# TermWylPomp1_ds18.net
KiCad netlist of a schematic drawn in Altium Designer
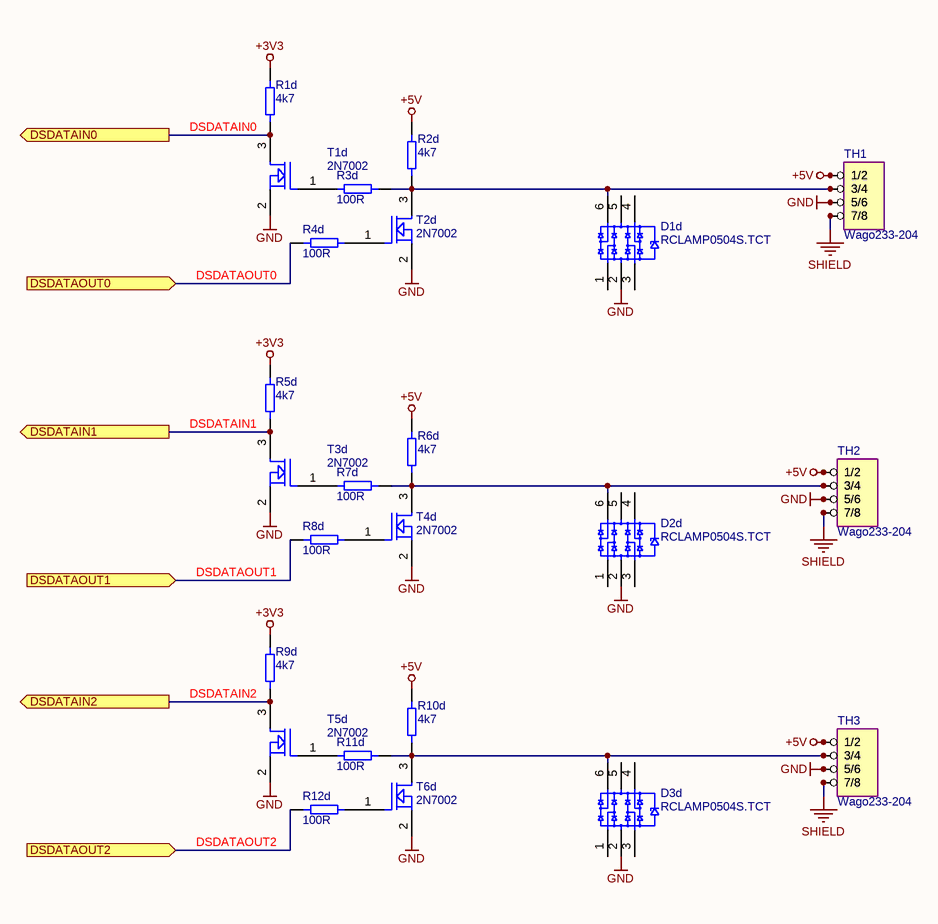
[diagram p0: TermWylPomp1_ds18.SchDoc]

(export (version "E")
  (design (tool "Eeschema 10.0.6"))
  (components
    (comp (ref "D1d")
      (value "RCLAMP0504S.TCT")
      (footprint "SOT23-6")
      (libsource (lib "PartsMySQL") (part "RCLAMP0504"))
    )
    (comp (ref "D2d")
      (value "RCLAMP0504S.TCT")
      (footprint "SOT23-6")
      (libsource (lib "PartsMySQL") (part "RCLAMP0504"))
    )
    (comp (ref "D3d")
      (value "RCLAMP0504S.TCT")
      (footprint "SOT23-6")
      (libsource (lib "PartsMySQL") (part "RCLAMP0504"))
    )
    (comp (ref "R1d") (value "4k7") (footprint "0805R") (libsource (lib "PartsMySQL") (part "R")))
    (comp (ref "R2d") (value "4k7") (footprint "0805R") (libsource (lib "PartsMySQL") (part "R")))
    (comp (ref "R3d") (value "100R") (footprint "0805R") (libsource (lib "PartsMySQL") (part "R")))
    (comp (ref "R4d") (value "100R") (footprint "0805R") (libsource (lib "PartsMySQL") (part "R")))
    (comp (ref "R5d") (value "4k7") (footprint "0805R") (libsource (lib "PartsMySQL") (part "R")))
    (comp (ref "R6d") (value "4k7") (footprint "0805R") (libsource (lib "PartsMySQL") (part "R")))
    (comp (ref "R7d") (value "100R") (footprint "0805R") (libsource (lib "PartsMySQL") (part "R")))
    (comp (ref "R8d") (value "100R") (footprint "0805R") (libsource (lib "PartsMySQL") (part "R")))
    (comp (ref "R9d") (value "4k7") (footprint "0805R") (libsource (lib "PartsMySQL") (part "R")))
    (comp (ref "R10d") (value "4k7") (footprint "0805R") (libsource (lib "PartsMySQL") (part "R")))
    (comp (ref "R11d") (value "100R") (footprint "0805R") (libsource (lib "PartsMySQL") (part "R")))
    (comp (ref "R12d") (value "100R") (footprint "0805R") (libsource (lib "PartsMySQL") (part "R")))
    (comp (ref "T1d")
      (value "2N7002")
      (footprint "SOT23-3")
      (libsource (lib "PartsMySQL") (part "MOSFET_N_SOT23-3"))
    )
    (comp (ref "T2d")
      (value "2N7002")
      (footprint "SOT23-3")
      (libsource (lib "PartsMySQL") (part "MOSFET_N_SOT23-3"))
    )
    (comp (ref "T3d")
      (value "2N7002")
      (footprint "SOT23-3")
      (libsource (lib "PartsMySQL") (part "MOSFET_N_SOT23-3"))
    )
    (comp (ref "T4d")
      (value "2N7002")
      (footprint "SOT23-3")
      (libsource (lib "PartsMySQL") (part "MOSFET_N_SOT23-3"))
    )
    (comp (ref "T5d")
      (value "2N7002")
      (footprint "SOT23-3")
      (libsource (lib "PartsMySQL") (part "MOSFET_N_SOT23-3"))
    )
    (comp (ref "T6d")
      (value "2N7002")
      (footprint "SOT23-3")
      (libsource (lib "PartsMySQL") (part "MOSFET_N_SOT23-3"))
    )
    (comp (ref "TH1")
      (value "Wago233-204")
      (footprint "Wago233-204")
      (libsource (lib "PartsMySQL") (part "Wago233-204"))
    )
    (comp (ref "TH2")
      (value "Wago233-204")
      (footprint "Wago233-204")
      (libsource (lib "PartsMySQL") (part "Wago233-204"))
    )
    (comp (ref "TH3")
      (value "Wago233-204")
      (footprint "Wago233-204")
      (libsource (lib "PartsMySQL") (part "Wago233-204"))
    )
  )
  (nets
    (net (code "1") (name "+3V3") (class "Default")
      (node (ref "R1d") (pin "1") (pinfunction "1_1") (pintype "passive"))
      (node (ref "R5d") (pin "1") (pinfunction "1_1") (pintype "passive"))
      (node (ref "R9d") (pin "1") (pinfunction "1_1") (pintype "passive"))
    )
    (net (code "2") (name "+5V") (class "Default")
      (node (ref "R10d") (pin "1") (pinfunction "1_1") (pintype "passive"))
      (node (ref "R2d") (pin "1") (pinfunction "1_1") (pintype "passive"))
      (node (ref "R6d") (pin "1") (pinfunction "1_1") (pintype "passive"))
      (node (ref "TH1") (pin "1") (pinfunction "1/2_1") (pintype "passive"))
      (node (ref "TH1") (pin "2") (pinfunction "1/2_2") (pintype "passive"))
      (node (ref "TH2") (pin "1") (pinfunction "1/2_1") (pintype "passive"))
      (node (ref "TH2") (pin "2") (pinfunction "1/2_2") (pintype "passive"))
      (node (ref "TH3") (pin "1") (pinfunction "1/2_1") (pintype "passive"))
      (node (ref "TH3") (pin "2") (pinfunction "1/2_2") (pintype "passive"))
    )
    (net (code "3") (name "/DSDATAIN0") (class "Default")
      (node (ref "R1d") (pin "2") (pinfunction "2_2") (pintype "passive"))
      (node (ref "T1d") (pin "3") (pinfunction "DRAIN_3") (pintype "passive"))
    )
    (net (code "4") (name "/DSDATAIN1") (class "Default")
      (node (ref "R5d") (pin "2") (pinfunction "2_2") (pintype "passive"))
      (node (ref "T3d") (pin "3") (pinfunction "DRAIN_3") (pintype "passive"))
    )
    (net (code "5") (name "/DSDATAIN2") (class "Default")
      (node (ref "R9d") (pin "2") (pinfunction "2_2") (pintype "passive"))
      (node (ref "T5d") (pin "3") (pinfunction "DRAIN_3") (pintype "passive"))
    )
    (net (code "6") (name "/DSDATAOUT0") (class "Default")
      (node (ref "R4d") (pin "1") (pinfunction "1_1") (pintype "passive"))
    )
    (net (code "7") (name "/DSDATAOUT1") (class "Default")
      (node (ref "R8d") (pin "1") (pinfunction "1_1") (pintype "passive"))
    )
    (net (code "8") (name "/DSDATAOUT2") (class "Default")
      (node (ref "R12d") (pin "1") (pinfunction "1_1") (pintype "passive"))
    )
    (net (code "9") (name "GND") (class "Default")
      (node (ref "D1d") (pin "2") (pinfunction "2_2") (pintype "passive"))
      (node (ref "D2d") (pin "2") (pinfunction "2_2") (pintype "passive"))
      (node (ref "D3d") (pin "2") (pinfunction "2_2") (pintype "passive"))
      (node (ref "T1d") (pin "2") (pinfunction "SOURCE_2") (pintype "passive"))
      (node (ref "T2d") (pin "2") (pinfunction "SOURCE_2") (pintype "passive"))
      (node (ref "T3d") (pin "2") (pinfunction "SOURCE_2") (pintype "passive"))
      (node (ref "T4d") (pin "2") (pinfunction "SOURCE_2") (pintype "passive"))
      (node (ref "T5d") (pin "2") (pinfunction "SOURCE_2") (pintype "passive"))
      (node (ref "T6d") (pin "2") (pinfunction "SOURCE_2") (pintype "passive"))
      (node (ref "TH1") (pin "5") (pinfunction "5/6_5") (pintype "passive"))
      (node (ref "TH1") (pin "6") (pinfunction "5/6_6") (pintype "passive"))
      (node (ref "TH2") (pin "5") (pinfunction "5/6_5") (pintype "passive"))
      (node (ref "TH2") (pin "6") (pinfunction "5/6_6") (pintype "passive"))
      (node (ref "TH3") (pin "5") (pinfunction "5/6_5") (pintype "passive"))
      (node (ref "TH3") (pin "6") (pinfunction "5/6_6") (pintype "passive"))
    )
    (net (code "10") (name "Net-(T1d-GATE)") (class "Default")
      (node (ref "R3d") (pin "1") (pinfunction "1_1") (pintype "passive"))
      (node (ref "T1d") (pin "1") (pinfunction "GATE_1") (pintype "passive"))
    )
    (net (code "11") (name "Net-(T2d-DRAIN)") (class "Default")
      (node (ref "D1d") (pin "6") (pinfunction "6_6") (pintype "passive"))
      (node (ref "R2d") (pin "2") (pinfunction "2_2") (pintype "passive"))
      (node (ref "R3d") (pin "2") (pinfunction "2_2") (pintype "passive"))
      (node (ref "T2d") (pin "3") (pinfunction "DRAIN_3") (pintype "passive"))
      (node (ref "TH1") (pin "3") (pinfunction "3/4_3") (pintype "passive"))
      (node (ref "TH1") (pin "4") (pinfunction "3/4_4") (pintype "passive"))
    )
    (net (code "12") (name "Net-(T2d-GATE)") (class "Default")
      (node (ref "R4d") (pin "2") (pinfunction "2_2") (pintype "passive"))
      (node (ref "T2d") (pin "1") (pinfunction "GATE_1") (pintype "passive"))
    )
    (net (code "13") (name "Net-(T3d-GATE)") (class "Default")
      (node (ref "R7d") (pin "1") (pinfunction "1_1") (pintype "passive"))
      (node (ref "T3d") (pin "1") (pinfunction "GATE_1") (pintype "passive"))
    )
    (net (code "14") (name "Net-(T4d-DRAIN)") (class "Default")
      (node (ref "D2d") (pin "6") (pinfunction "6_6") (pintype "passive"))
      (node (ref "R6d") (pin "2") (pinfunction "2_2") (pintype "passive"))
      (node (ref "R7d") (pin "2") (pinfunction "2_2") (pintype "passive"))
      (node (ref "T4d") (pin "3") (pinfunction "DRAIN_3") (pintype "passive"))
      (node (ref "TH2") (pin "3") (pinfunction "3/4_3") (pintype "passive"))
      (node (ref "TH2") (pin "4") (pinfunction "3/4_4") (pintype "passive"))
    )
    (net (code "15") (name "Net-(T4d-GATE)") (class "Default")
      (node (ref "R8d") (pin "2") (pinfunction "2_2") (pintype "passive"))
      (node (ref "T4d") (pin "1") (pinfunction "GATE_1") (pintype "passive"))
    )
    (net (code "16") (name "Net-(T5d-GATE)") (class "Default")
      (node (ref "R11d") (pin "1") (pinfunction "1_1") (pintype "passive"))
      (node (ref "T5d") (pin "1") (pinfunction "GATE_1") (pintype "passive"))
    )
    (net (code "17") (name "Net-(T6d-DRAIN)") (class "Default")
      (node (ref "D3d") (pin "6") (pinfunction "6_6") (pintype "passive"))
      (node (ref "R10d") (pin "2") (pinfunction "2_2") (pintype "passive"))
      (node (ref "R11d") (pin "2") (pinfunction "2_2") (pintype "passive"))
      (node (ref "T6d") (pin "3") (pinfunction "DRAIN_3") (pintype "passive"))
      (node (ref "TH3") (pin "3") (pinfunction "3/4_3") (pintype "passive"))
      (node (ref "TH3") (pin "4") (pinfunction "3/4_4") (pintype "passive"))
    )
    (net (code "18") (name "Net-(T6d-GATE)") (class "Default")
      (node (ref "R12d") (pin "2") (pinfunction "2_2") (pintype "passive"))
      (node (ref "T6d") (pin "1") (pinfunction "GATE_1") (pintype "passive"))
    )
    (net (code "19") (name "SHIELD") (class "Default")
      (node (ref "TH1") (pin "7") (pinfunction "7/8_7") (pintype "passive"))
      (node (ref "TH1") (pin "8") (pinfunction "7/8_8") (pintype "passive"))
      (node (ref "TH2") (pin "7") (pinfunction "7/8_7") (pintype "passive"))
      (node (ref "TH2") (pin "8") (pinfunction "7/8_8") (pintype "passive"))
      (node (ref "TH3") (pin "7") (pinfunction "7/8_7") (pintype "passive"))
      (node (ref "TH3") (pin "8") (pinfunction "7/8_8") (pintype "passive"))
    )
    (net (code "20") (name "unconnected-(D1d-Pad1)") (class "Default")
      (node (ref "D1d") (pin "1") (pinfunction "1_1") (pintype "passive"))
    )
    (net (code "21") (name "unconnected-(D1d-Pad3)") (class "Default")
      (node (ref "D1d") (pin "3") (pinfunction "3_3") (pintype "passive"))
    )
    (net (code "22") (name "unconnected-(D1d-Pad4)") (class "Default")
      (node (ref "D1d") (pin "4") (pinfunction "4_4") (pintype "passive"))
    )
    (net (code "23") (name "unconnected-(D1d-Pad5)") (class "Default")
      (node (ref "D1d") (pin "5") (pinfunction "5_5") (pintype "passive"))
    )
    (net (code "24") (name "unconnected-(D2d-Pad1)") (class "Default")
      (node (ref "D2d") (pin "1") (pinfunction "1_1") (pintype "passive"))
    )
    (net (code "25") (name "unconnected-(D2d-Pad3)") (class "Default")
      (node (ref "D2d") (pin "3") (pinfunction "3_3") (pintype "passive"))
    )
    (net (code "26") (name "unconnected-(D2d-Pad4)") (class "Default")
      (node (ref "D2d") (pin "4") (pinfunction "4_4") (pintype "passive"))
    )
    (net (code "27") (name "unconnected-(D2d-Pad5)") (class "Default")
      (node (ref "D2d") (pin "5") (pinfunction "5_5") (pintype "passive"))
    )
    (net (code "28") (name "unconnected-(D3d-Pad1)") (class "Default")
      (node (ref "D3d") (pin "1") (pinfunction "1_1") (pintype "passive"))
    )
    (net (code "29") (name "unconnected-(D3d-Pad3)") (class "Default")
      (node (ref "D3d") (pin "3") (pinfunction "3_3") (pintype "passive"))
    )
    (net (code "30") (name "unconnected-(D3d-Pad4)") (class "Default")
      (node (ref "D3d") (pin "4") (pinfunction "4_4") (pintype "passive"))
    )
    (net (code "31") (name "unconnected-(D3d-Pad5)") (class "Default")
      (node (ref "D3d") (pin "5") (pinfunction "5_5") (pintype "passive"))
    )
  )
)
